# Main_Board.net
KiCad netlist of a schematic drawn in EAGLE
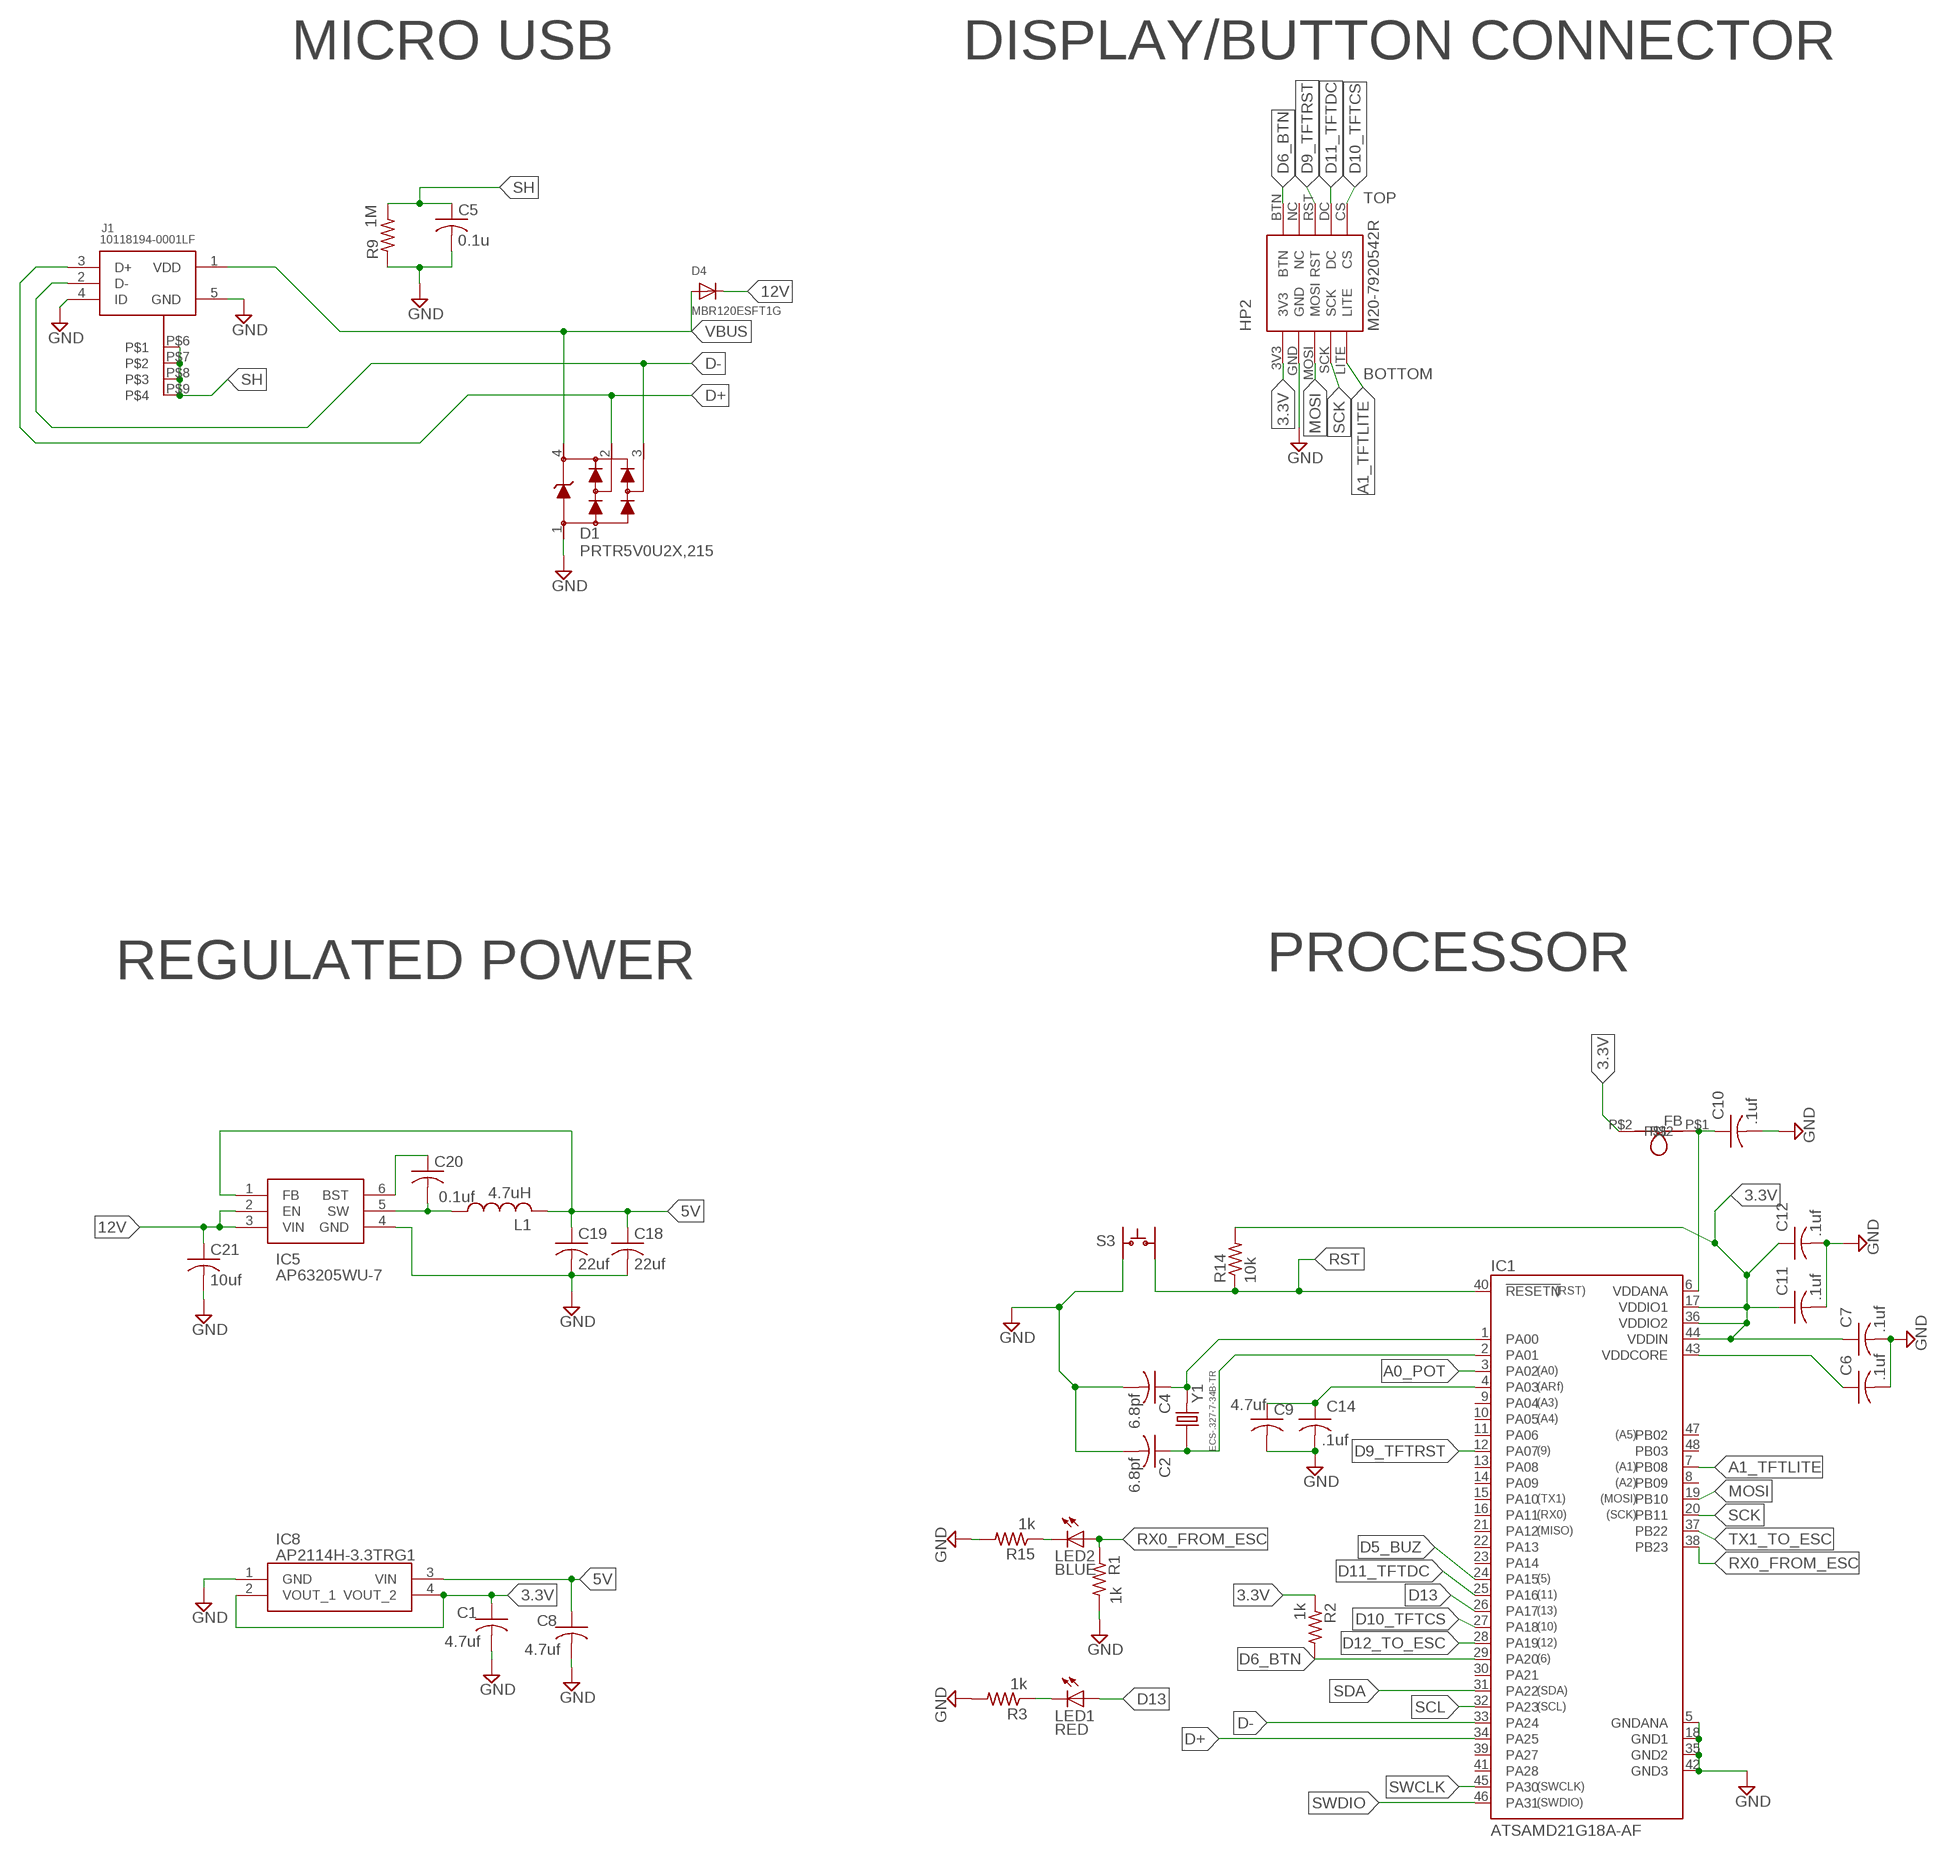
[diagram p0: schematic, sheet 1, part 1 of 2]
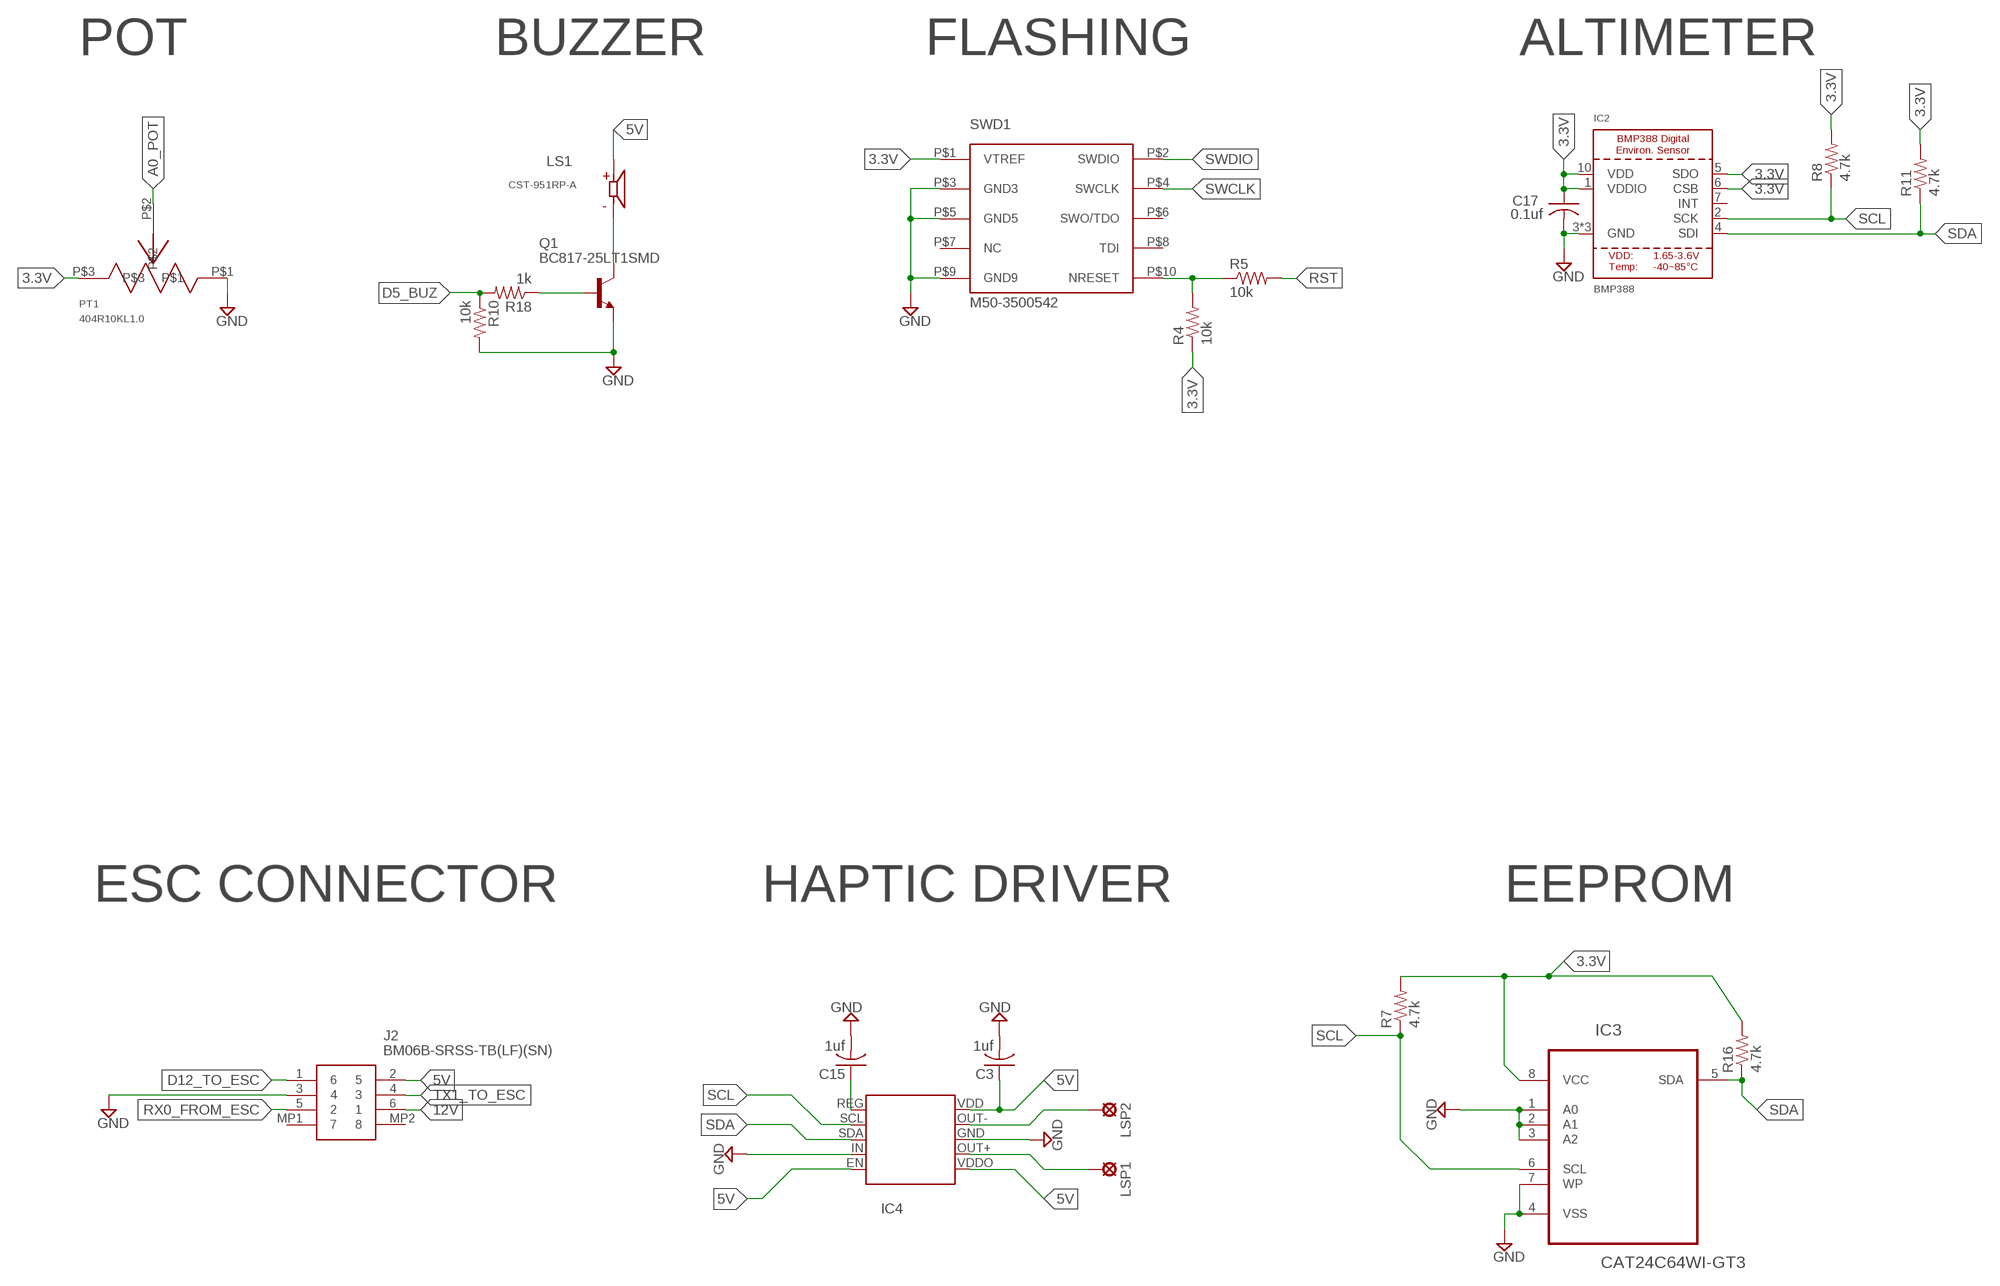
[diagram p1: schematic, sheet 1, part 2 of 2]

(export (version "E")
  (design (tool "Eeschema 10.0.6"))
  (components
    (comp (ref "C1")
      (value "4.7uf")
      (footprint "eagle-import:C0402")
      (libsource (lib "eagle-import") (part "C-USC0402"))
    )
    (comp (ref "C2")
      (value "6.8pf")
      (footprint "eagle-import:C0402")
      (libsource (lib "eagle-import") (part "C-USC0402"))
    )
    (comp (ref "C3")
      (value "1uf")
      (footprint "eagle-import:C0402")
      (libsource (lib "eagle-import") (part "C-USC0402"))
    )
    (comp (ref "C4")
      (value "6.8pf")
      (footprint "eagle-import:C0402")
      (libsource (lib "eagle-import") (part "C-USC0402"))
    )
    (comp (ref "C5")
      (value "0.1u")
      (footprint "eagle-import:C0402")
      (libsource (lib "eagle-import") (part "C-USC0402"))
    )
    (comp (ref "C6")
      (value ".1uf")
      (footprint "eagle-import:C0402")
      (libsource (lib "eagle-import") (part "C-USC0402"))
    )
    (comp (ref "C7")
      (value ".1uf")
      (footprint "eagle-import:C0402")
      (libsource (lib "eagle-import") (part "C-USC0402"))
    )
    (comp (ref "C8")
      (value "4.7uf")
      (footprint "eagle-import:C0402")
      (libsource (lib "eagle-import") (part "C-USC0402"))
    )
    (comp (ref "C9")
      (value "4.7uf")
      (footprint "eagle-import:C0402")
      (libsource (lib "eagle-import") (part "C-USC0402"))
    )
    (comp (ref "C10")
      (value ".1uf")
      (footprint "eagle-import:C0402")
      (libsource (lib "eagle-import") (part "C-USC0402"))
    )
    (comp (ref "C11")
      (value ".1uf")
      (footprint "eagle-import:C0402")
      (libsource (lib "eagle-import") (part "C-USC0402"))
    )
    (comp (ref "C12")
      (value ".1uf")
      (footprint "eagle-import:C0402")
      (libsource (lib "eagle-import") (part "C-USC0402"))
    )
    (comp (ref "C14")
      (value ".1uf")
      (footprint "eagle-import:C0402")
      (libsource (lib "eagle-import") (part "C-USC0402"))
    )
    (comp (ref "C15")
      (value "1uf")
      (footprint "eagle-import:C0402")
      (libsource (lib "eagle-import") (part "C-USC0402"))
    )
    (comp (ref "C17")
      (value "0.1uf")
      (footprint "eagle-import:C0402")
      (libsource (lib "eagle-import") (part "C-USC0402"))
    )
    (comp (ref "C18")
      (value "22uf")
      (footprint "eagle-import:C0603")
      (libsource (lib "eagle-import") (part "C-USC0603"))
    )
    (comp (ref "C19")
      (value "22uf")
      (footprint "eagle-import:C0603")
      (libsource (lib "eagle-import") (part "C-USC0603"))
    )
    (comp (ref "C20")
      (value "0.1uf")
      (footprint "eagle-import:C0402")
      (libsource (lib "eagle-import") (part "C-USC0402"))
    )
    (comp (ref "C21")
      (value "10uf")
      (footprint "eagle-import:C0805")
      (libsource (lib "eagle-import") (part "C-USC0805"))
    )
    (comp (ref "D1")
      (value "PRTR5V0U2X,215")
      (footprint "eagle-import:SOT143B")
      (fields (field (name "MF") "Nexperia"))
      (libsource (lib "eagle-import") (part "PRTR5V0U2X,215"))
    )
    (comp (ref "D4")
      (value "MBR120ESFT1G")
      (footprint "eagle-import:SOD-123FL")
      (libsource (lib "eagle-import") (part "DIODE_SOD-123FL"))
    )
    (comp (ref "FB")
      (value "BLM18PG471SN1D")
      (footprint "eagle-import:FERRITE_BEAD")
      (libsource (lib "eagle-import") (part "FERRITE_BEAD"))
    )
    (comp (ref "HP2")
      (value "M20-7920542R")
      (footprint "eagle-import:M20-7920542R")
      (libsource (lib "eagle-import") (part "M20-7920542R"))
    )
    (comp (ref "IC1")
      (value "ATSAMD21G18A-AF")
      (footprint "eagle-import:QFP50P900X900X120-48N")
      (fields (field (name "DIGI-KEY_PART_NUMBER") "ATSAMD21G18A-AF-ND") (field (name "MF") "Microchip"))
      (libsource (lib "eagle-import") (part "ATSAMD21G18A-AF"))
    )
    (comp (ref "IC2")
      (value "BMP388")
      (footprint "eagle-import:BMP388")
      (libsource (lib "eagle-import") (part "BMP388"))
    )
    (comp (ref "IC3")
      (value "CAT24C64WI-GT3")
      (footprint "eagle-import:SOIC127P600X175-8N")
      (fields (field (name "MF") "ON Semiconductor"))
      (libsource (lib "eagle-import") (part "CAT24C64WI-GT3"))
    )
    (comp (ref "IC4")
      (value "DRV2605")
      (footprint "eagle-import:DRV2605")
      (libsource (lib "eagle-import") (part "DRV2605"))
    )
    (comp (ref "IC5")
      (value "AP63205WU-7")
      (footprint "eagle-import:SOT95P280X100-6N")
      (fields (field (name "MOUSER_PART_NUMBER") "621-AP63205WU-7"))
      (libsource (lib "eagle-import") (part "AP63205WU-7"))
    )
    (comp (ref "IC8")
      (value "AP2114H-3.3TRG1")
      (footprint "eagle-import:SOT230P700X180-4N")
      (fields
        (field (name "MOUSER_PART_NUMBER") "621-AP2114H-3.3TRG1")
        (field (name "RS_PART_NUMBER") "8283528P")
      )
      (libsource (lib "eagle-import") (part "AP2114H-3.3TRG1"))
    )
    (comp (ref "J1")
      (value "10118194-0001LF")
      (footprint "eagle-import:FRAMATOME_10118194-0001LF")
      (fields (field (name "MF") "Amphenol FCI"))
      (libsource (lib "eagle-import") (part "10118194-0001LF"))
    )
    (comp (ref "J2")
      (value "BM06B-SRSS-TB(LF)(SN)")
      (footprint "eagle-import:BM06BSRSSTBLFSN")
      (fields (field (name "RS_PART_NUMBER") "5468782"))
      (libsource (lib "eagle-import") (part "BM06B-SRSS-TB(LF)(SN)"))
    )
    (comp (ref "L1")
      (value "4.7uH")
      (footprint "eagle-import:L1812")
      (libsource (lib "eagle-import") (part "L-USL1812"))
    )
    (comp (ref "LED1")
      (value "RED")
      (footprint "eagle-import:CHIP-LED0603")
      (libsource (lib "eagle-import") (part "LEDCHIP-LED0603"))
    )
    (comp (ref "LED2")
      (value "BLUE")
      (footprint "eagle-import:CHIP-LED0603")
      (libsource (lib "eagle-import") (part "LEDCHIP-LED0603"))
    )
    (comp (ref "LS1")
      (value "CST-951RP-A")
      (footprint "eagle-import:CUI_CST-951RP-A")
      (fields (field (name "MF") "CUI Inc."))
      (libsource (lib "eagle-import") (part "CST-951RP-A"))
    )
    (comp (ref "LSP1")
      (value "SE14")
      (footprint "eagle-import:SE14")
      (libsource (lib "eagle-import") (part "SE14"))
    )
    (comp (ref "LSP2")
      (value "SE14")
      (footprint "eagle-import:SE14")
      (libsource (lib "eagle-import") (part "SE14"))
    )
    (comp (ref "PT1")
      (value "404R10KL1.0")
      (footprint "eagle-import:404R10KL1.0")
      (libsource (lib "eagle-import") (part "404R10KL1.0"))
    )
    (comp (ref "Q1")
      (value "BC817-25LT1SMD")
      (footprint "eagle-import:SOT23-BEC")
      (libsource (lib "eagle-import") (part "BC817SMD-25LT1"))
    )
    (comp (ref "R1")
      (value "1k")
      (footprint "eagle-import:R0402")
      (libsource (lib "eagle-import") (part "R-US_R0402"))
    )
    (comp (ref "R2")
      (value "1k")
      (footprint "eagle-import:R0402")
      (libsource (lib "eagle-import") (part "R-US_R0402"))
    )
    (comp (ref "R3")
      (value "1k")
      (footprint "eagle-import:R0402")
      (libsource (lib "eagle-import") (part "R-US_R0402"))
    )
    (comp (ref "R4")
      (value "10k")
      (footprint "eagle-import:R0402")
      (libsource (lib "eagle-import") (part "R-US_R0402"))
    )
    (comp (ref "R5")
      (value "10k")
      (footprint "eagle-import:R0402")
      (libsource (lib "eagle-import") (part "R-US_R0402"))
    )
    (comp (ref "R7")
      (value "4.7k")
      (footprint "eagle-import:R0402")
      (libsource (lib "eagle-import") (part "R-US_R0402"))
    )
    (comp (ref "R8")
      (value "4.7k")
      (footprint "eagle-import:R0402")
      (libsource (lib "eagle-import") (part "R-US_R0402"))
    )
    (comp (ref "R9")
      (value "1M")
      (footprint "eagle-import:R0402")
      (libsource (lib "eagle-import") (part "R-US_R0402"))
    )
    (comp (ref "R10")
      (value "10k")
      (footprint "eagle-import:R0402")
      (libsource (lib "eagle-import") (part "R-US_R0402"))
    )
    (comp (ref "R11")
      (value "4.7k")
      (footprint "eagle-import:R0402")
      (libsource (lib "eagle-import") (part "R-US_R0402"))
    )
    (comp (ref "R14")
      (value "10k")
      (footprint "eagle-import:R0402")
      (libsource (lib "eagle-import") (part "R-US_R0402"))
    )
    (comp (ref "R15")
      (value "1k")
      (footprint "eagle-import:R0402")
      (libsource (lib "eagle-import") (part "R-US_R0402"))
    )
    (comp (ref "R16")
      (value "4.7k")
      (footprint "eagle-import:R0402")
      (libsource (lib "eagle-import") (part "R-US_R0402"))
    )
    (comp (ref "R18")
      (value "1k")
      (footprint "eagle-import:R0402")
      (libsource (lib "eagle-import") (part "R-US_R0402"))
    )
    (comp (ref "S3")
      (value "KMR231NG LFS")
      (footprint "eagle-import:TATILE_SWITCH")
      (libsource (lib "eagle-import") (part "TACTILE_SWITCH"))
    )
    (comp (ref "SWD1")
      (value "M50-3500542")
      (footprint "eagle-import:M50-3500542")
      (libsource (lib "eagle-import") (part "M50-3500542"))
    )
    (comp (ref "Y1")
      (value "ECS-.327-7-34B-TR")
      (footprint "eagle-import:XTAL_ECS-.327-12.5-34B-C-TR")
      (fields (field (name "MF") "ECS International"))
      (libsource (lib "eagle-import") (part "ECS-.327-7-34B-TR"))
    )
  )
  (nets
    (net (code "1") (name "3.3V") (class "Default")
      (node (ref "C1") (pin "1") (pinfunction "1_1") (pintype "passive"))
      (node (ref "C11") (pin "1") (pinfunction "1_1") (pintype "passive"))
      (node (ref "C12") (pin "1") (pinfunction "1_1") (pintype "passive"))
      (node (ref "C17") (pin "1") (pinfunction "1_1") (pintype "passive"))
      (node (ref "C7") (pin "1") (pinfunction "1_1") (pintype "passive"))
      (node (ref "FB") (pin "P$2") (pinfunction "P$2_P$2") (pintype "bidirectional"))
      (node (ref "HP2") (pin "3V3") (pinfunction "3V3_3V3") (pintype "bidirectional"))
      (node (ref "IC1") (pin "17") (pinfunction "VDDIO1_17") (pintype "power_in"))
      (node (ref "IC1") (pin "36") (pinfunction "VDDIO2_36") (pintype "power_in"))
      (node (ref "IC1") (pin "44") (pinfunction "VDDIN_44") (pintype "power_in"))
      (node (ref "IC2") (pin "1") (pinfunction "VDDIO_1") (pintype "power_in"))
      (node (ref "IC2") (pin "10") (pinfunction "VDD_10") (pintype "power_in"))
      (node (ref "IC2") (pin "5") (pinfunction "SDO_5") (pintype "output"))
      (node (ref "IC2") (pin "6") (pinfunction "CSB_6") (pintype "input"))
      (node (ref "IC3") (pin "8") (pinfunction "VCC_8") (pintype "power_in"))
      (node (ref "IC8") (pin "2") (pinfunction "VOUT_1_2") (pintype "bidirectional"))
      (node (ref "IC8") (pin "4") (pinfunction "VOUT_2_4") (pintype "bidirectional"))
      (node (ref "PT1") (pin "P$3") (pinfunction "P$3_P$3") (pintype "bidirectional"))
      (node (ref "R11") (pin "2") (pinfunction "2_2") (pintype "passive"))
      (node (ref "R14") (pin "2") (pinfunction "2_2") (pintype "passive"))
      (node (ref "R16") (pin "2") (pinfunction "2_2") (pintype "passive"))
      (node (ref "R2") (pin "1") (pinfunction "1_1") (pintype "passive"))
      (node (ref "R4") (pin "1") (pinfunction "1_1") (pintype "passive"))
      (node (ref "R7") (pin "2") (pinfunction "2_2") (pintype "passive"))
      (node (ref "R8") (pin "2") (pinfunction "2_2") (pintype "passive"))
      (node (ref "SWD1") (pin "P$1") (pinfunction "VTREF_P$1") (pintype "bidirectional"))
    )
    (net (code "2") (name "5V") (class "Default")
      (node (ref "C18") (pin "1") (pinfunction "1_1") (pintype "passive"))
      (node (ref "C19") (pin "1") (pinfunction "1_1") (pintype "passive"))
      (node (ref "C3") (pin "1") (pinfunction "1_1") (pintype "passive"))
      (node (ref "C8") (pin "1") (pinfunction "1_1") (pintype "passive"))
      (node (ref "IC4") (pin "EN") (pinfunction "EN_EN") (pintype "bidirectional"))
      (node (ref "IC4") (pin "VDD") (pinfunction "VDD_VDD") (pintype "bidirectional"))
      (node (ref "IC4") (pin "VDDO") (pinfunction "VDDO_VDDO") (pintype "bidirectional"))
      (node (ref "IC5") (pin "1") (pinfunction "FB_1") (pintype "bidirectional"))
      (node (ref "IC8") (pin "3") (pinfunction "VIN_3") (pintype "bidirectional"))
      (node (ref "J2") (pin "2") (pinfunction "5_2") (pintype "bidirectional"))
      (node (ref "L1") (pin "2") (pinfunction "2_2") (pintype "passive"))
      (node (ref "LS1") (pin "P") (pinfunction "P_P") (pintype "passive"))
    )
    (net (code "3") (name "12V") (class "Default")
      (node (ref "C21") (pin "1") (pinfunction "1_1") (pintype "passive"))
      (node (ref "D4") (pin "C") (pinfunction "C_C") (pintype "passive"))
      (node (ref "IC5") (pin "2") (pinfunction "EN_2") (pintype "bidirectional"))
      (node (ref "IC5") (pin "3") (pinfunction "VIN_3") (pintype "bidirectional"))
      (node (ref "J2") (pin "6") (pinfunction "1_6") (pintype "bidirectional"))
    )
    (net (code "4") (name "A0_POT") (class "Default")
      (node (ref "IC1") (pin "3") (pinfunction "PA02_3") (pintype "bidirectional"))
      (node (ref "PT1") (pin "P$2") (pinfunction "P$2_P$2") (pintype "bidirectional"))
    )
    (net (code "5") (name "A1_TFTLITE") (class "Default")
      (node (ref "HP2") (pin "LITE") (pinfunction "LITE_LITE") (pintype "bidirectional"))
      (node (ref "IC1") (pin "7") (pinfunction "PB08_7") (pintype "bidirectional"))
    )
    (net (code "6") (name "D+") (class "Default")
      (node (ref "D1") (pin "2") (pinfunction "P$2_2") (pintype "passive"))
      (node (ref "IC1") (pin "34") (pinfunction "PA25_34") (pintype "bidirectional"))
      (node (ref "J1") (pin "3") (pinfunction "D+_3") (pintype "bidirectional"))
    )
    (net (code "7") (name "D-") (class "Default")
      (node (ref "D1") (pin "3") (pinfunction "P$3_3") (pintype "passive"))
      (node (ref "IC1") (pin "33") (pinfunction "PA24_33") (pintype "bidirectional"))
      (node (ref "J1") (pin "2") (pinfunction "D-_2") (pintype "bidirectional"))
    )
    (net (code "8") (name "D5_BUZ") (class "Default")
      (node (ref "IC1") (pin "24") (pinfunction "PA15_24") (pintype "bidirectional"))
      (node (ref "R10") (pin "1") (pinfunction "1_1") (pintype "passive"))
      (node (ref "R18") (pin "2") (pinfunction "2_2") (pintype "passive"))
    )
    (net (code "9") (name "D6_BTN") (class "Default")
      (node (ref "HP2") (pin "BTN") (pinfunction "BTN_BTN") (pintype "bidirectional"))
      (node (ref "IC1") (pin "29") (pinfunction "PA20_29") (pintype "bidirectional"))
      (node (ref "R2") (pin "2") (pinfunction "2_2") (pintype "passive"))
    )
    (net (code "10") (name "D9_TFTRST") (class "Default")
      (node (ref "HP2") (pin "RST") (pinfunction "RST_RST") (pintype "bidirectional"))
      (node (ref "IC1") (pin "12") (pinfunction "PA07_12") (pintype "bidirectional"))
    )
    (net (code "11") (name "D10_TFTCS") (class "Default")
      (node (ref "HP2") (pin "CS") (pinfunction "CS_CS") (pintype "bidirectional"))
      (node (ref "IC1") (pin "27") (pinfunction "PA18_27") (pintype "bidirectional"))
    )
    (net (code "12") (name "D11_TFTDC") (class "Default")
      (node (ref "HP2") (pin "DC") (pinfunction "DC_DC") (pintype "bidirectional"))
      (node (ref "IC1") (pin "25") (pinfunction "PA16_25") (pintype "bidirectional"))
    )
    (net (code "13") (name "D12_TO_ESC") (class "Default")
      (node (ref "IC1") (pin "28") (pinfunction "PA19_28") (pintype "bidirectional"))
      (node (ref "J2") (pin "1") (pinfunction "6_1") (pintype "bidirectional"))
    )
    (net (code "14") (name "D13") (class "Default")
      (node (ref "IC1") (pin "26") (pinfunction "PA17_26") (pintype "bidirectional"))
      (node (ref "LED1") (pin "A") (pinfunction "A_A") (pintype "passive"))
    )
    (net (code "15") (name "GND") (class "Default")
      (node (ref "C1") (pin "2") (pinfunction "2_2") (pintype "passive"))
      (node (ref "C10") (pin "2") (pinfunction "2_2") (pintype "passive"))
      (node (ref "C11") (pin "2") (pinfunction "2_2") (pintype "passive"))
      (node (ref "C12") (pin "2") (pinfunction "2_2") (pintype "passive"))
      (node (ref "C14") (pin "2") (pinfunction "2_2") (pintype "passive"))
      (node (ref "C15") (pin "2") (pinfunction "2_2") (pintype "passive"))
      (node (ref "C17") (pin "2") (pinfunction "2_2") (pintype "passive"))
      (node (ref "C18") (pin "2") (pinfunction "2_2") (pintype "passive"))
      (node (ref "C19") (pin "2") (pinfunction "2_2") (pintype "passive"))
      (node (ref "C2") (pin "2") (pinfunction "2_2") (pintype "passive"))
      (node (ref "C21") (pin "2") (pinfunction "2_2") (pintype "passive"))
      (node (ref "C3") (pin "2") (pinfunction "2_2") (pintype "passive"))
      (node (ref "C4") (pin "2") (pinfunction "2_2") (pintype "passive"))
      (node (ref "C5") (pin "2") (pinfunction "2_2") (pintype "passive"))
      (node (ref "C6") (pin "2") (pinfunction "2_2") (pintype "passive"))
      (node (ref "C7") (pin "2") (pinfunction "2_2") (pintype "passive"))
      (node (ref "C8") (pin "2") (pinfunction "2_2") (pintype "passive"))
      (node (ref "C9") (pin "2") (pinfunction "2_2") (pintype "passive"))
      (node (ref "D1") (pin "1") (pinfunction "P$1_1") (pintype "passive"))
      (node (ref "HP2") (pin "GND") (pinfunction "GND_GND") (pintype "bidirectional"))
      (node (ref "IC1") (pin "18") (pinfunction "GND1_18") (pintype "power_in"))
      (node (ref "IC1") (pin "35") (pinfunction "GND2_35") (pintype "power_in"))
      (node (ref "IC1") (pin "42") (pinfunction "GND3_42") (pintype "power_in"))
      (node (ref "IC1") (pin "5") (pinfunction "GNDANA_5") (pintype "power_in"))
      (node (ref "IC2") (pin "3") (pinfunction "GND_3") (pintype "power_in"))
      (node (ref "IC2") (pin "8") (pinfunction "GND_8") (pintype "power_in"))
      (node (ref "IC2") (pin "9") (pinfunction "GND_9") (pintype "power_in"))
      (node (ref "IC3") (pin "1") (pinfunction "A0_1") (pintype "input"))
      (node (ref "IC3") (pin "2") (pinfunction "A1_2") (pintype "input"))
      (node (ref "IC3") (pin "3") (pinfunction "A2_3") (pintype "input"))
      (node (ref "IC3") (pin "4") (pinfunction "VSS_4") (pintype "passive"))
      (node (ref "IC3") (pin "7") (pinfunction "WP_7") (pintype "input"))
      (node (ref "IC4") (pin "GND") (pinfunction "GND_GND") (pintype "bidirectional"))
      (node (ref "IC4") (pin "IN") (pinfunction "IN_IN") (pintype "bidirectional"))
      (node (ref "IC5") (pin "4") (pinfunction "GND_4") (pintype "bidirectional"))
      (node (ref "IC8") (pin "1") (pinfunction "GND_1") (pintype "bidirectional"))
      (node (ref "J1") (pin "4") (pinfunction "ID_4") (pintype "passive"))
      (node (ref "J1") (pin "5") (pinfunction "GND_5") (pintype "power_in"))
      (node (ref "J2") (pin "3") (pinfunction "4_3") (pintype "bidirectional"))
      (node (ref "PT1") (pin "P$1") (pinfunction "P$1_P$1") (pintype "bidirectional"))
      (node (ref "Q1") (pin "E") (pinfunction "E_E") (pintype "passive"))
      (node (ref "R1") (pin "2") (pinfunction "2_2") (pintype "passive"))
      (node (ref "R10") (pin "2") (pinfunction "2_2") (pintype "passive"))
      (node (ref "R15") (pin "2") (pinfunction "2_2") (pintype "passive"))
      (node (ref "R3") (pin "2") (pinfunction "2_2") (pintype "passive"))
      (node (ref "R9") (pin "1") (pinfunction "1_1") (pintype "passive"))
      (node (ref "S3") (pin "P$3") (pinfunction "P$3_P$3") (pintype "bidirectional"))
      (node (ref "SWD1") (pin "P$3") (pinfunction "GND3_P$3") (pintype "bidirectional"))
      (node (ref "SWD1") (pin "P$5") (pinfunction "GND5_P$5") (pintype "bidirectional"))
      (node (ref "SWD1") (pin "P$9") (pinfunction "GND9_P$9") (pintype "bidirectional"))
    )
    (net (code "16") (name "MOSI") (class "Default")
      (node (ref "HP2") (pin "MOSI") (pinfunction "MOSI_MOSI") (pintype "bidirectional"))
      (node (ref "IC1") (pin "19") (pinfunction "PB10_19") (pintype "bidirectional"))
    )
    (net (code "17") (name "Net-(C15-Pad1)") (class "Default")
      (node (ref "C15") (pin "1") (pinfunction "1_1") (pintype "passive"))
      (node (ref "IC4") (pin "REG") (pinfunction "REG_REG") (pintype "bidirectional"))
    )
    (net (code "18") (name "Net-(IC1-PA00)") (class "Default")
      (node (ref "C4") (pin "1") (pinfunction "1_1") (pintype "passive"))
      (node (ref "IC1") (pin "1") (pinfunction "PA00_1") (pintype "bidirectional"))
      (node (ref "Y1") (pin "2") (pinfunction "2_2") (pintype "passive"))
    )
    (net (code "19") (name "Net-(IC1-PA01)") (class "Default")
      (node (ref "C2") (pin "1") (pinfunction "1_1") (pintype "passive"))
      (node (ref "IC1") (pin "2") (pinfunction "PA01_2") (pintype "bidirectional"))
      (node (ref "Y1") (pin "1") (pinfunction "1_1") (pintype "passive"))
    )
    (net (code "20") (name "Net-(IC1-PA03)") (class "Default")
      (node (ref "C14") (pin "1") (pinfunction "1_1") (pintype "passive"))
      (node (ref "C9") (pin "1") (pinfunction "1_1") (pintype "passive"))
      (node (ref "IC1") (pin "4") (pinfunction "PA03_4") (pintype "bidirectional"))
    )
    (net (code "21") (name "Net-(IC1-VDDANA)") (class "Default")
      (node (ref "C10") (pin "1") (pinfunction "1_1") (pintype "passive"))
      (node (ref "FB") (pin "P$1") (pinfunction "P$1_P$1") (pintype "bidirectional"))
      (node (ref "IC1") (pin "6") (pinfunction "VDDANA_6") (pintype "power_in"))
    )
    (net (code "22") (name "Net-(IC1-VDDCORE)") (class "Default")
      (node (ref "C6") (pin "1") (pinfunction "1_1") (pintype "passive"))
      (node (ref "IC1") (pin "43") (pinfunction "VDDCORE_43") (pintype "power_in"))
    )
    (net (code "23") (name "Net-(IC4-PadOUT+)") (class "Default")
      (node (ref "IC4") (pin "OUT+") (pinfunction "OUT+_OUT+") (pintype "bidirectional"))
      (node (ref "LSP1") (pin "MP") (pinfunction "MP_MP") (pintype "passive"))
    )
    (net (code "24") (name "Net-(IC4-PadOUT-)") (class "Default")
      (node (ref "IC4") (pin "OUT-") (pinfunction "OUT-_OUT-") (pintype "bidirectional"))
      (node (ref "LSP2") (pin "MP") (pinfunction "MP_MP") (pintype "passive"))
    )
    (net (code "25") (name "Net-(IC5-BST)") (class "Default")
      (node (ref "C20") (pin "1") (pinfunction "1_1") (pintype "passive"))
      (node (ref "IC5") (pin "6") (pinfunction "BST_6") (pintype "bidirectional"))
    )
    (net (code "26") (name "Net-(IC5-SW)") (class "Default")
      (node (ref "C20") (pin "2") (pinfunction "2_2") (pintype "passive"))
      (node (ref "IC5") (pin "5") (pinfunction "SW_5") (pintype "bidirectional"))
      (node (ref "L1") (pin "1") (pinfunction "1_1") (pintype "passive"))
    )
    (net (code "27") (name "Net-(LED1-PadC)") (class "Default")
      (node (ref "LED1") (pin "C") (pinfunction "C_C") (pintype "passive"))
      (node (ref "R3") (pin "1") (pinfunction "1_1") (pintype "passive"))
    )
    (net (code "28") (name "Net-(LED2-PadC)") (class "Default")
      (node (ref "LED2") (pin "C") (pinfunction "C_C") (pintype "passive"))
      (node (ref "R15") (pin "1") (pinfunction "1_1") (pintype "passive"))
    )
    (net (code "29") (name "Net-(LS1-PadM)") (class "Default")
      (node (ref "LS1") (pin "M") (pinfunction "M_M") (pintype "passive"))
      (node (ref "Q1") (pin "C") (pinfunction "C_C") (pintype "passive"))
    )
    (net (code "30") (name "Net-(Q1-PadB)") (class "Default")
      (node (ref "Q1") (pin "B") (pinfunction "B_B") (pintype "passive"))
      (node (ref "R18") (pin "1") (pinfunction "1_1") (pintype "passive"))
    )
    (net (code "31") (name "Net-(SWD1-NRESET)") (class "Default")
      (node (ref "R4") (pin "2") (pinfunction "2_2") (pintype "passive"))
      (node (ref "R5") (pin "1") (pinfunction "1_1") (pintype "passive"))
      (node (ref "SWD1") (pin "P$10") (pinfunction "NRESET_P$10") (pintype "bidirectional"))
    )
    (net (code "32") (name "RST") (class "Default")
      (node (ref "IC1") (pin "40") (pinfunction "~{RESETN}_40") (pintype "input"))
      (node (ref "R14") (pin "1") (pinfunction "1_1") (pintype "passive"))
      (node (ref "R5") (pin "2") (pinfunction "2_2") (pintype "passive"))
      (node (ref "S3") (pin "P$4") (pinfunction "P$4_P$4") (pintype "bidirectional"))
    )
    (net (code "33") (name "RX0_FROM_ESC") (class "Default")
      (node (ref "IC1") (pin "38") (pinfunction "PB23_38") (pintype "bidirectional"))
      (node (ref "J2") (pin "5") (pinfunction "2_5") (pintype "bidirectional"))
      (node (ref "LED2") (pin "A") (pinfunction "A_A") (pintype "passive"))
      (node (ref "R1") (pin "1") (pinfunction "1_1") (pintype "passive"))
    )
    (net (code "34") (name "SCK") (class "Default")
      (node (ref "HP2") (pin "SCK") (pinfunction "SCK_SCK") (pintype "bidirectional"))
      (node (ref "IC1") (pin "20") (pinfunction "PB11_20") (pintype "bidirectional"))
    )
    (net (code "35") (name "SCL") (class "Default")
      (node (ref "IC1") (pin "32") (pinfunction "PA23_32") (pintype "bidirectional"))
      (node (ref "IC2") (pin "2") (pinfunction "SCK_2") (pintype "input"))
      (node (ref "IC3") (pin "6") (pinfunction "SCL_6") (pintype "input"))
      (node (ref "IC4") (pin "SCL") (pinfunction "SCL_SCL") (pintype "bidirectional"))
      (node (ref "R7") (pin "1") (pinfunction "1_1") (pintype "passive"))
      (node (ref "R8") (pin "1") (pinfunction "1_1") (pintype "passive"))
    )
    (net (code "36") (name "SDA") (class "Default")
      (node (ref "IC1") (pin "31") (pinfunction "PA22_31") (pintype "bidirectional"))
      (node (ref "IC2") (pin "4") (pinfunction "SDI_4") (pintype "input"))
      (node (ref "IC3") (pin "5") (pinfunction "SDA_5") (pintype "bidirectional"))
      (node (ref "IC4") (pin "SDA") (pinfunction "SDA_SDA") (pintype "bidirectional"))
      (node (ref "R11") (pin "1") (pinfunction "1_1") (pintype "passive"))
      (node (ref "R16") (pin "1") (pinfunction "1_1") (pintype "passive"))
    )
    (net (code "37") (name "SH") (class "Default")
      (node (ref "C5") (pin "1") (pinfunction "1_1") (pintype "passive"))
      (node (ref "J1") (pin "P$6") (pinfunction "P$1_P$6") (pintype "bidirectional"))
      (node (ref "J1") (pin "P$7") (pinfunction "P$2_P$7") (pintype "bidirectional"))
      (node (ref "J1") (pin "P$8") (pinfunction "P$3_P$8") (pintype "bidirectional"))
      (node (ref "J1") (pin "P$9") (pinfunction "P$4_P$9") (pintype "bidirectional"))
      (node (ref "R9") (pin "2") (pinfunction "2_2") (pintype "passive"))
    )
    (net (code "38") (name "SWCLK") (class "Default")
      (node (ref "IC1") (pin "45") (pinfunction "PA30_45") (pintype "bidirectional"))
      (node (ref "SWD1") (pin "P$4") (pinfunction "SWCLK_P$4") (pintype "bidirectional"))
    )
    (net (code "39") (name "SWDIO") (class "Default")
      (node (ref "IC1") (pin "46") (pinfunction "PA31_46") (pintype "bidirectional"))
      (node (ref "SWD1") (pin "P$2") (pinfunction "SWDIO_P$2") (pintype "bidirectional"))
    )
    (net (code "40") (name "TX1_TO_ESC") (class "Default")
      (node (ref "IC1") (pin "37") (pinfunction "PB22_37") (pintype "bidirectional"))
      (node (ref "J2") (pin "4") (pinfunction "3_4") (pintype "bidirectional"))
    )
    (net (code "41") (name "VBUS") (class "Default")
      (node (ref "D1") (pin "4") (pinfunction "P$4_4") (pintype "passive"))
      (node (ref "D4") (pin "A") (pinfunction "A_A") (pintype "passive"))
      (node (ref "J1") (pin "1") (pinfunction "VDD_1") (pintype "power_in"))
    )
    (net (code "42") (name "unconnected-(HP2-PadNC)") (class "Default")
      (node (ref "HP2") (pin "NC") (pinfunction "NC_NC") (pintype "bidirectional"))
    )
    (net (code "43") (name "unconnected-(IC1-PA04-Pad9)") (class "Default")
      (node (ref "IC1") (pin "9") (pinfunction "PA04_9") (pintype "bidirectional"))
    )
    (net (code "44") (name "unconnected-(IC1-PA05-Pad10)") (class "Default")
      (node (ref "IC1") (pin "10") (pinfunction "PA05_10") (pintype "bidirectional"))
    )
    (net (code "45") (name "unconnected-(IC1-PA06-Pad11)") (class "Default")
      (node (ref "IC1") (pin "11") (pinfunction "PA06_11") (pintype "bidirectional"))
    )
    (net (code "46") (name "unconnected-(IC1-PA08-Pad13)") (class "Default")
      (node (ref "IC1") (pin "13") (pinfunction "PA08_13") (pintype "bidirectional"))
    )
    (net (code "47") (name "unconnected-(IC1-PA09-Pad14)") (class "Default")
      (node (ref "IC1") (pin "14") (pinfunction "PA09_14") (pintype "bidirectional"))
    )
    (net (code "48") (name "unconnected-(IC1-PA10-Pad15)") (class "Default")
      (node (ref "IC1") (pin "15") (pinfunction "PA10_15") (pintype "bidirectional"))
    )
    (net (code "49") (name "unconnected-(IC1-PA11-Pad16)") (class "Default")
      (node (ref "IC1") (pin "16") (pinfunction "PA11_16") (pintype "bidirectional"))
    )
    (net (code "50") (name "unconnected-(IC1-PA12-Pad21)") (class "Default")
      (node (ref "IC1") (pin "21") (pinfunction "PA12_21") (pintype "bidirectional"))
    )
    (net (code "51") (name "unconnected-(IC1-PA13-Pad22)") (class "Default")
      (node (ref "IC1") (pin "22") (pinfunction "PA13_22") (pintype "bidirectional"))
    )
    (net (code "52") (name "unconnected-(IC1-PA14-Pad23)") (class "Default")
      (node (ref "IC1") (pin "23") (pinfunction "PA14_23") (pintype "bidirectional"))
    )
    (net (code "53") (name "unconnected-(IC1-PA21-Pad30)") (class "Default")
      (node (ref "IC1") (pin "30") (pinfunction "PA21_30") (pintype "bidirectional"))
    )
    (net (code "54") (name "unconnected-(IC1-PA27-Pad39)") (class "Default")
      (node (ref "IC1") (pin "39") (pinfunction "PA27_39") (pintype "bidirectional"))
    )
    (net (code "55") (name "unconnected-(IC1-PA28-Pad41)") (class "Default")
      (node (ref "IC1") (pin "41") (pinfunction "PA28_41") (pintype "bidirectional"))
    )
    (net (code "56") (name "unconnected-(IC1-PB02-Pad47)") (class "Default")
      (node (ref "IC1") (pin "47") (pinfunction "PB02_47") (pintype "bidirectional"))
    )
    (net (code "57") (name "unconnected-(IC1-PB03-Pad48)") (class "Default")
      (node (ref "IC1") (pin "48") (pinfunction "PB03_48") (pintype "bidirectional"))
    )
    (net (code "58") (name "unconnected-(IC1-PB09-Pad8)") (class "Default")
      (node (ref "IC1") (pin "8") (pinfunction "PB09_8") (pintype "bidirectional"))
    )
    (net (code "59") (name "unconnected-(IC2-INT-Pad7)") (class "Default")
      (node (ref "IC2") (pin "7") (pinfunction "INT_7") (pintype "output"))
    )
    (net (code "60") (name "unconnected-(J2-7-PadMP1)") (class "Default")
      (node (ref "J2") (pin "MP1") (pinfunction "7_MP1") (pintype "bidirectional"))
    )
    (net (code "61") (name "unconnected-(J2-8-PadMP2)") (class "Default")
      (node (ref "J2") (pin "MP2") (pinfunction "8_MP2") (pintype "bidirectional"))
    )
    (net (code "62") (name "unconnected-(S3-PadP$1)") (class "Default")
      (node (ref "S3") (pin "P$1") (pinfunction "P$1_P$1") (pintype "bidirectional"))
    )
    (net (code "63") (name "unconnected-(S3-PadP$2)") (class "Default")
      (node (ref "S3") (pin "P$2") (pinfunction "P$2_P$2") (pintype "bidirectional"))
    )
    (net (code "64") (name "unconnected-(SWD1-NC-PadP$7)") (class "Default")
      (node (ref "SWD1") (pin "P$7") (pinfunction "NC_P$7") (pintype "bidirectional"))
    )
    (net (code "65") (name "unconnected-(SWD1-SWO{slash}TDO-PadP$6)") (class "Default")
      (node (ref "SWD1") (pin "P$6") (pinfunction "SWO/TDO_P$6") (pintype "bidirectional"))
    )
    (net (code "66") (name "unconnected-(SWD1-TDI-PadP$8)") (class "Default")
      (node (ref "SWD1") (pin "P$8") (pinfunction "TDI_P$8") (pintype "bidirectional"))
    )
  )
)
